# hacker-boards-refactor.net
KiCad netlist of a schematic drawn in EAGLE
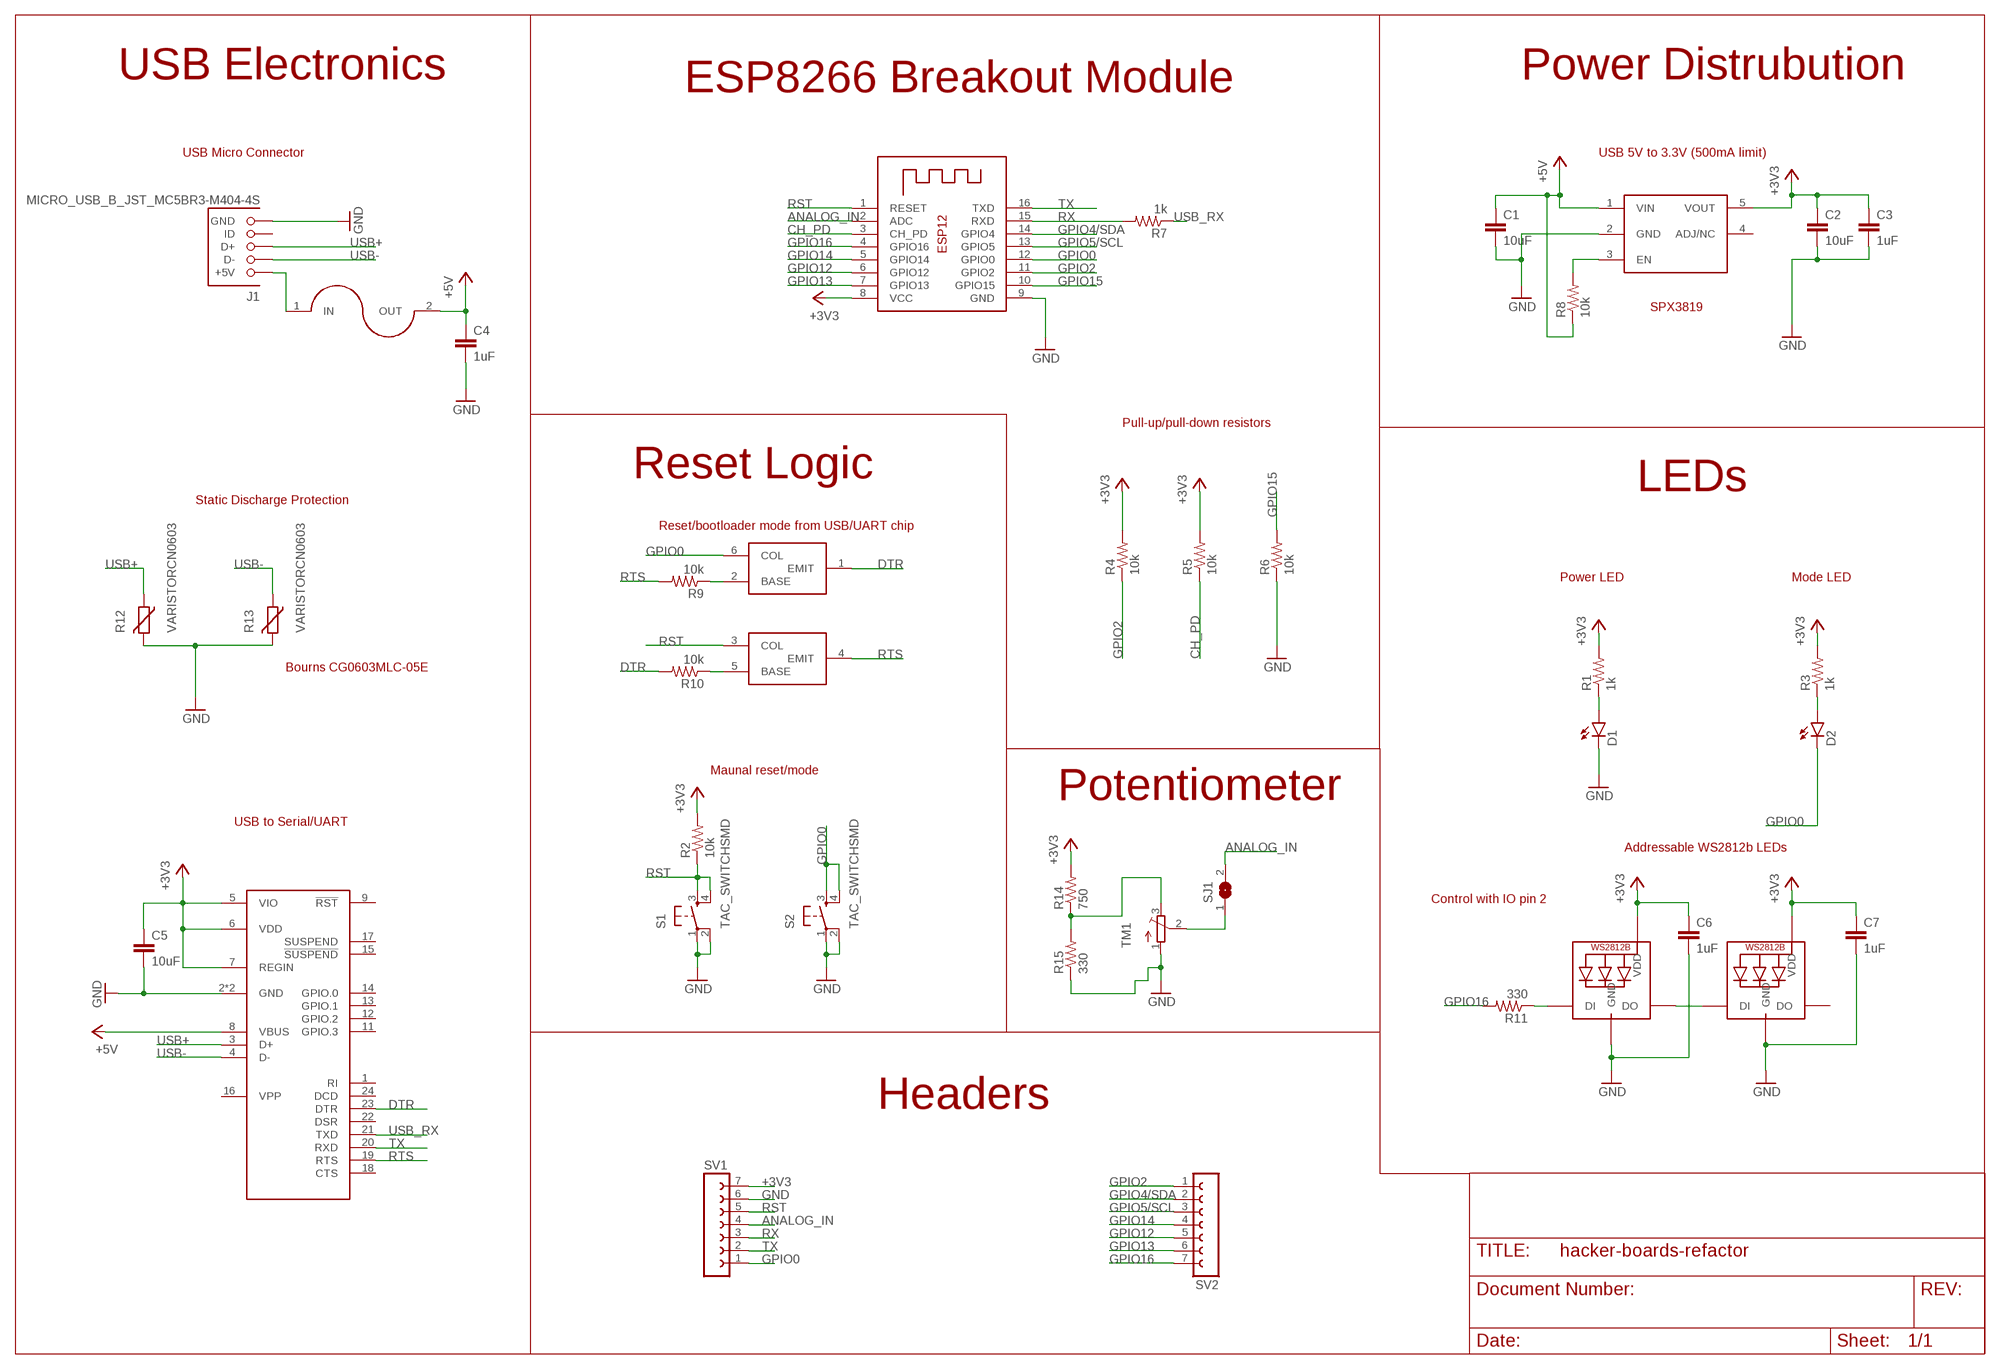
[diagram p0: schematic, sheet 1]

(export (version "E")
  (design (tool "Eeschema 10.0.6"))
  (components
    (comp (ref "C1")
      (value "10uF")
      (footprint "eagle-import:C0805")
      (libsource (lib "eagle-import") (part "C0805"))
    )
    (comp (ref "C2")
      (value "10uF")
      (footprint "eagle-import:C0805")
      (libsource (lib "eagle-import") (part "C0805"))
    )
    (comp (ref "C3")
      (value "1uF")
      (footprint "eagle-import:C0805")
      (libsource (lib "eagle-import") (part "C0805"))
    )
    (comp (ref "C4")
      (value "1uF")
      (footprint "eagle-import:C0805")
      (libsource (lib "eagle-import") (part "C0805"))
    )
    (comp (ref "C5")
      (value "10uF")
      (footprint "eagle-import:C0805")
      (libsource (lib "eagle-import") (part "C0805"))
    )
    (comp (ref "C6")
      (value "1uF")
      (footprint "eagle-import:C0805")
      (libsource (lib "eagle-import") (part "C0805"))
    )
    (comp (ref "C7")
      (value "1uF")
      (footprint "eagle-import:C0805")
      (libsource (lib "eagle-import") (part "C0805"))
    )
    (comp (ref "D1")
      (value "LED0603")
      (footprint "eagle-import:LED-0603")
      (libsource (lib "eagle-import") (part "LED0603"))
    )
    (comp (ref "D2")
      (value "LED0603")
      (footprint "eagle-import:LED-0603")
      (libsource (lib "eagle-import") (part "LED0603"))
    )
    (comp (ref "J1")
      (value "MICRO_USB_B_JST_MC5BR3-M404-4S")
      (footprint "eagle-import:USB_MICRO_B-JST-MC5BR3-M404-4S-TB")
      (libsource (lib "eagle-import") (part "MICRO_USB_B_JST_MC5BR3-M404-4S"))
    )
    (comp (ref "LED1")
      (value "WS2812B5050")
      (footprint "eagle-import:WS2812B")
      (libsource (lib "eagle-import") (part "WS2812B5050"))
    )
    (comp (ref "LED2")
      (value "WS2812B5050")
      (footprint "eagle-import:WS2812B")
      (libsource (lib "eagle-import") (part "WS2812B5050"))
    )
    (comp (ref "R1")
      (value "1k")
      (footprint "eagle-import:R0805")
      (libsource (lib "eagle-import") (part "R-US_R0805"))
    )
    (comp (ref "R2")
      (value "10k")
      (footprint "eagle-import:R0805")
      (libsource (lib "eagle-import") (part "R-US_R0805"))
    )
    (comp (ref "R3")
      (value "1k")
      (footprint "eagle-import:R0805")
      (libsource (lib "eagle-import") (part "R-US_R0805"))
    )
    (comp (ref "R4")
      (value "10k")
      (footprint "eagle-import:R0805")
      (libsource (lib "eagle-import") (part "R-US_R0805"))
    )
    (comp (ref "R5")
      (value "10k")
      (footprint "eagle-import:R0805")
      (libsource (lib "eagle-import") (part "R-US_R0805"))
    )
    (comp (ref "R6")
      (value "10k")
      (footprint "eagle-import:R0805")
      (libsource (lib "eagle-import") (part "R-US_R0805"))
    )
    (comp (ref "R7")
      (value "1k")
      (footprint "eagle-import:R0805")
      (libsource (lib "eagle-import") (part "R-US_R0805"))
    )
    (comp (ref "R8")
      (value "10k")
      (footprint "eagle-import:R0805")
      (libsource (lib "eagle-import") (part "R-US_R0805"))
    )
    (comp (ref "R9")
      (value "10k")
      (footprint "eagle-import:R0805")
      (libsource (lib "eagle-import") (part "R-US_R0805"))
    )
    (comp (ref "R10")
      (value "10k")
      (footprint "eagle-import:R0805")
      (libsource (lib "eagle-import") (part "R-US_R0805"))
    )
    (comp (ref "R11")
      (value "330")
      (footprint "eagle-import:R0805")
      (libsource (lib "eagle-import") (part "R-US_R0805"))
    )
    (comp (ref "R12")
      (value "VARISTORCN0603")
      (footprint "eagle-import:CT_CN0603")
      (libsource (lib "eagle-import") (part "VARISTORCN0603"))
    )
    (comp (ref "R13")
      (value "VARISTORCN0603")
      (footprint "eagle-import:CT_CN0603")
      (libsource (lib "eagle-import") (part "VARISTORCN0603"))
    )
    (comp (ref "R14")
      (value "750")
      (footprint "eagle-import:R0805")
      (libsource (lib "eagle-import") (part "R-US_R0805"))
    )
    (comp (ref "R15")
      (value "330")
      (footprint "eagle-import:R0805")
      (libsource (lib "eagle-import") (part "R-US_R0805"))
    )
    (comp (ref "S1")
      (value "TAC_SWITCHSMD")
      (footprint "eagle-import:TACTILE-SWITCH-SMD")
      (libsource (lib "eagle-import") (part "TAC_SWITCHSMD"))
    )
    (comp (ref "S2")
      (value "TAC_SWITCHSMD")
      (footprint "eagle-import:TACTILE-SWITCH-SMD")
      (libsource (lib "eagle-import") (part "TAC_SWITCHSMD"))
    )
    (comp (ref "SJ1") (value "SJ") (footprint "eagle-import:SJ") (libsource (lib "eagle-import") (part "SJ")))
    (comp (ref "SV1")
      (value "FE07-1")
      (footprint "eagle-import:FE07")
      (libsource (lib "eagle-import") (part "FE07-1"))
    )
    (comp (ref "SV2")
      (value "FE07-1")
      (footprint "eagle-import:FE07")
      (libsource (lib "eagle-import") (part "FE07-1"))
    )
    (comp (ref "TM1")
      (value "TRIMPOTTC33X")
      (footprint "eagle-import:TC33X")
      (libsource (lib "eagle-import") (part "TRIMPOTTC33X"))
    )
    (comp (ref "U$1")
      (value "USB-FUSE")
      (footprint "eagle-import:L1812")
      (libsource (lib "eagle-import") (part "USB-FUSE"))
    )
    (comp (ref "U$2")
      (value "AP2112")
      (footprint "eagle-import:SOT23-5L")
      (libsource (lib "eagle-import") (part "AP2112"))
    )
    (comp (ref "U$3")
      (value "CP2104")
      (footprint "eagle-import:QFN24_4X4")
      (libsource (lib "eagle-import") (part "CP2104"))
    )
    (comp (ref "U$4")
      (value "MBT3904DW1T1G")
      (footprint "eagle-import:SOT363")
      (libsource (lib "eagle-import") (part "MBT3904DW1T1G"))
    )
    (comp (ref "X1")
      (value "ESP-12")
      (footprint "eagle-import:ESP-12")
      (libsource (lib "eagle-import") (part "ESP-12"))
    )
  )
  (nets
    (net (code "1") (name "+3V3") (class "Default")
      (node (ref "C2") (pin "1") (pinfunction "1_1") (pintype "passive"))
      (node (ref "C3") (pin "1") (pinfunction "1_1") (pintype "passive"))
      (node (ref "C5") (pin "1") (pinfunction "1_1") (pintype "passive"))
      (node (ref "C6") (pin "1") (pinfunction "1_1") (pintype "passive"))
      (node (ref "C7") (pin "1") (pinfunction "1_1") (pintype "passive"))
      (node (ref "LED1") (pin "1-VDD") (pinfunction "VDD_1-VDD") (pintype "power_in"))
      (node (ref "LED2") (pin "1-VDD") (pinfunction "VDD_1-VDD") (pintype "power_in"))
      (node (ref "R1") (pin "2") (pinfunction "2_2") (pintype "passive"))
      (node (ref "R14") (pin "2") (pinfunction "2_2") (pintype "passive"))
      (node (ref "R2") (pin "2") (pinfunction "2_2") (pintype "passive"))
      (node (ref "R3") (pin "2") (pinfunction "2_2") (pintype "passive"))
      (node (ref "R4") (pin "2") (pinfunction "2_2") (pintype "passive"))
      (node (ref "R5") (pin "2") (pinfunction "2_2") (pintype "passive"))
      (node (ref "SV1") (pin "7") (pinfunction "7_7") (pintype "passive"))
      (node (ref "U$2") (pin "5") (pinfunction "VOUT_5") (pintype "bidirectional"))
      (node (ref "U$3") (pin "5") (pinfunction "VIO_5") (pintype "bidirectional"))
      (node (ref "U$3") (pin "6") (pinfunction "VDD_6") (pintype "bidirectional"))
      (node (ref "U$3") (pin "7") (pinfunction "REGIN_7") (pintype "bidirectional"))
      (node (ref "X1") (pin "8") (pinfunction "VCC_8") (pintype "power_in"))
    )
    (net (code "2") (name "+5V") (class "Default")
      (node (ref "C1") (pin "1") (pinfunction "1_1") (pintype "passive"))
      (node (ref "C4") (pin "1") (pinfunction "1_1") (pintype "passive"))
      (node (ref "R8") (pin "1") (pinfunction "1_1") (pintype "passive"))
      (node (ref "U$1") (pin "2") (pinfunction "OUT_2") (pintype "bidirectional"))
      (node (ref "U$2") (pin "1") (pinfunction "VIN_1") (pintype "bidirectional"))
      (node (ref "U$3") (pin "8") (pinfunction "VBUS_8") (pintype "bidirectional"))
    )
    (net (code "3") (name "/ANALOG_IN") (class "Default")
      (node (ref "SJ1") (pin "2") (pinfunction "2_2") (pintype "passive"))
      (node (ref "SV1") (pin "4") (pinfunction "4_4") (pintype "passive"))
      (node (ref "X1") (pin "2") (pinfunction "ADC_2") (pintype "passive"))
    )
    (net (code "4") (name "/CH_PD") (class "Default")
      (node (ref "R5") (pin "1") (pinfunction "1_1") (pintype "passive"))
      (node (ref "X1") (pin "3") (pinfunction "CH_PD_3") (pintype "input"))
    )
    (net (code "5") (name "/DTR") (class "Default")
      (node (ref "R10") (pin "2") (pinfunction "2_2") (pintype "passive"))
      (node (ref "U$3") (pin "23") (pinfunction "DTR_23") (pintype "bidirectional"))
      (node (ref "U$4") (pin "1") (pinfunction "EMIT_1") (pintype "bidirectional"))
    )
    (net (code "6") (name "/GPIO0") (class "Default")
      (node (ref "D2") (pin "C") (pinfunction "C_C") (pintype "passive"))
      (node (ref "S2") (pin "3") (pinfunction "3_3") (pintype "passive"))
      (node (ref "S2") (pin "4") (pinfunction "4_4") (pintype "passive"))
      (node (ref "SV1") (pin "1") (pinfunction "1_1") (pintype "passive"))
      (node (ref "U$4") (pin "6") (pinfunction "COL_6") (pintype "bidirectional"))
      (node (ref "X1") (pin "12") (pinfunction "GPIO0_12") (pintype "bidirectional"))
    )
    (net (code "7") (name "/GPIO2") (class "Default")
      (node (ref "R4") (pin "1") (pinfunction "1_1") (pintype "passive"))
      (node (ref "SV2") (pin "1") (pinfunction "1_1") (pintype "passive"))
      (node (ref "X1") (pin "11") (pinfunction "GPIO2_11") (pintype "bidirectional"))
    )
    (net (code "8") (name "/GPIO4{slash}SDA") (class "Default")
      (node (ref "SV2") (pin "2") (pinfunction "2_2") (pintype "passive"))
      (node (ref "X1") (pin "14") (pinfunction "GPIO4_14") (pintype "bidirectional"))
    )
    (net (code "9") (name "/GPIO5{slash}SCL") (class "Default")
      (node (ref "SV2") (pin "3") (pinfunction "3_3") (pintype "passive"))
      (node (ref "X1") (pin "13") (pinfunction "GPIO5_13") (pintype "bidirectional"))
    )
    (net (code "10") (name "/GPIO12") (class "Default")
      (node (ref "SV2") (pin "5") (pinfunction "5_5") (pintype "passive"))
      (node (ref "X1") (pin "6") (pinfunction "GPIO12_6") (pintype "bidirectional"))
    )
    (net (code "11") (name "/GPIO13") (class "Default")
      (node (ref "SV2") (pin "6") (pinfunction "6_6") (pintype "passive"))
      (node (ref "X1") (pin "7") (pinfunction "GPIO13_7") (pintype "bidirectional"))
    )
    (net (code "12") (name "/GPIO14") (class "Default")
      (node (ref "SV2") (pin "4") (pinfunction "4_4") (pintype "passive"))
      (node (ref "X1") (pin "5") (pinfunction "GPIO14_5") (pintype "bidirectional"))
    )
    (net (code "13") (name "/GPIO15") (class "Default")
      (node (ref "R6") (pin "2") (pinfunction "2_2") (pintype "passive"))
      (node (ref "X1") (pin "10") (pinfunction "GPIO15_10") (pintype "bidirectional"))
    )
    (net (code "14") (name "/GPIO16") (class "Default")
      (node (ref "R11") (pin "2") (pinfunction "2_2") (pintype "passive"))
      (node (ref "SV2") (pin "7") (pinfunction "7_7") (pintype "passive"))
      (node (ref "X1") (pin "4") (pinfunction "GPIO16_4") (pintype "bidirectional"))
    )
    (net (code "15") (name "/RST") (class "Default")
      (node (ref "R2") (pin "1") (pinfunction "1_1") (pintype "passive"))
      (node (ref "S1") (pin "3") (pinfunction "3_3") (pintype "passive"))
      (node (ref "S1") (pin "4") (pinfunction "4_4") (pintype "passive"))
      (node (ref "SV1") (pin "5") (pinfunction "5_5") (pintype "passive"))
      (node (ref "U$4") (pin "3") (pinfunction "COL_3") (pintype "bidirectional"))
      (node (ref "X1") (pin "1") (pinfunction "RESET_1") (pintype "input"))
    )
    (net (code "16") (name "/RTS") (class "Default")
      (node (ref "R9") (pin "2") (pinfunction "2_2") (pintype "passive"))
      (node (ref "U$3") (pin "19") (pinfunction "RTS_19") (pintype "bidirectional"))
      (node (ref "U$4") (pin "4") (pinfunction "EMIT_4") (pintype "bidirectional"))
    )
    (net (code "17") (name "/RX") (class "Default")
      (node (ref "R7") (pin "2") (pinfunction "2_2") (pintype "passive"))
      (node (ref "SV1") (pin "3") (pinfunction "3_3") (pintype "passive"))
      (node (ref "X1") (pin "15") (pinfunction "RXD_15") (pintype "input"))
    )
    (net (code "18") (name "/TX") (class "Default")
      (node (ref "SV1") (pin "2") (pinfunction "2_2") (pintype "passive"))
      (node (ref "U$3") (pin "20") (pinfunction "RXD_20") (pintype "bidirectional"))
      (node (ref "X1") (pin "16") (pinfunction "TXD_16") (pintype "output"))
    )
    (net (code "19") (name "/USB+") (class "Default")
      (node (ref "J1") (pin "3") (pinfunction "D+_3") (pintype "bidirectional"))
      (node (ref "R12") (pin "1") (pinfunction "1_1") (pintype "passive"))
      (node (ref "U$3") (pin "3") (pinfunction "D+_3") (pintype "bidirectional"))
    )
    (net (code "20") (name "/USB-") (class "Default")
      (node (ref "J1") (pin "2") (pinfunction "D-_2") (pintype "bidirectional"))
      (node (ref "R13") (pin "1") (pinfunction "1_1") (pintype "passive"))
      (node (ref "U$3") (pin "4") (pinfunction "D-_4") (pintype "bidirectional"))
    )
    (net (code "21") (name "/USB_RX") (class "Default")
      (node (ref "R7") (pin "1") (pinfunction "1_1") (pintype "passive"))
      (node (ref "U$3") (pin "21") (pinfunction "TXD_21") (pintype "bidirectional"))
    )
    (net (code "22") (name "GND") (class "Default")
      (node (ref "C1") (pin "2") (pinfunction "2_2") (pintype "passive"))
      (node (ref "C2") (pin "2") (pinfunction "2_2") (pintype "passive"))
      (node (ref "C3") (pin "2") (pinfunction "2_2") (pintype "passive"))
      (node (ref "C4") (pin "2") (pinfunction "2_2") (pintype "passive"))
      (node (ref "C5") (pin "2") (pinfunction "2_2") (pintype "passive"))
      (node (ref "C6") (pin "2") (pinfunction "2_2") (pintype "passive"))
      (node (ref "C7") (pin "2") (pinfunction "2_2") (pintype "passive"))
      (node (ref "D1") (pin "C") (pinfunction "C_C") (pintype "passive"))
      (node (ref "J1") (pin "5") (pinfunction "GND_5") (pintype "bidirectional"))
      (node (ref "LED1") (pin "3-GND") (pinfunction "GND_3-GND") (pintype "power_in"))
      (node (ref "LED2") (pin "3-GND") (pinfunction "GND_3-GND") (pintype "power_in"))
      (node (ref "R12") (pin "2") (pinfunction "2_2") (pintype "passive"))
      (node (ref "R13") (pin "2") (pinfunction "2_2") (pintype "passive"))
      (node (ref "R15") (pin "1") (pinfunction "1_1") (pintype "passive"))
      (node (ref "R6") (pin "1") (pinfunction "1_1") (pintype "passive"))
      (node (ref "S1") (pin "1") (pinfunction "1_1") (pintype "passive"))
      (node (ref "S1") (pin "2") (pinfunction "2_2") (pintype "passive"))
      (node (ref "S2") (pin "1") (pinfunction "1_1") (pintype "passive"))
      (node (ref "S2") (pin "2") (pinfunction "2_2") (pintype "passive"))
      (node (ref "SV1") (pin "6") (pinfunction "6_6") (pintype "passive"))
      (node (ref "TM1") (pin "1") (pinfunction "A_1") (pintype "passive"))
      (node (ref "U$2") (pin "2") (pinfunction "GND_2") (pintype "bidirectional"))
      (node (ref "U$3") (pin "2") (pinfunction "GND_2") (pintype "bidirectional"))
      (node (ref "U$3") (pin "25") (pinfunction "GND_25") (pintype "bidirectional"))
      (node (ref "X1") (pin "9") (pinfunction "GND_9") (pintype "power_in"))
    )
    (net (code "23") (name "Net-(D1-PadA)") (class "Default")
      (node (ref "D1") (pin "A") (pinfunction "A_A") (pintype "passive"))
      (node (ref "R1") (pin "1") (pinfunction "1_1") (pintype "passive"))
    )
    (net (code "24") (name "Net-(D2-PadA)") (class "Default")
      (node (ref "D2") (pin "A") (pinfunction "A_A") (pintype "passive"))
      (node (ref "R3") (pin "1") (pinfunction "1_1") (pintype "passive"))
    )
    (net (code "25") (name "Net-(J1-+5V)") (class "Default")
      (node (ref "J1") (pin "1") (pinfunction "+5V_1") (pintype "bidirectional"))
      (node (ref "U$1") (pin "1") (pinfunction "IN_1") (pintype "bidirectional"))
    )
    (net (code "26") (name "Net-(LED1-DI)") (class "Default")
      (node (ref "LED1") (pin "4-DIN") (pinfunction "DI_4-DIN") (pintype "input"))
      (node (ref "R11") (pin "1") (pinfunction "1_1") (pintype "passive"))
    )
    (net (code "27") (name "Net-(LED1-DO)") (class "Default")
      (node (ref "LED1") (pin "2-DOUT") (pinfunction "DO_2-DOUT") (pintype "output"))
      (node (ref "LED2") (pin "4-DIN") (pinfunction "DI_4-DIN") (pintype "input"))
    )
    (net (code "28") (name "Net-(TM1-E)") (class "Default")
      (node (ref "R14") (pin "1") (pinfunction "1_1") (pintype "passive"))
      (node (ref "R15") (pin "2") (pinfunction "2_2") (pintype "passive"))
      (node (ref "TM1") (pin "3") (pinfunction "E_3") (pintype "passive"))
    )
    (net (code "29") (name "Net-(TM1-S)") (class "Default")
      (node (ref "SJ1") (pin "1") (pinfunction "1_1") (pintype "passive"))
      (node (ref "TM1") (pin "2") (pinfunction "S_2") (pintype "passive"))
    )
    (net (code "30") (name "Net-(U$2-EN)") (class "Default")
      (node (ref "R8") (pin "2") (pinfunction "2_2") (pintype "passive"))
      (node (ref "U$2") (pin "3") (pinfunction "EN_3") (pintype "bidirectional"))
    )
    (net (code "31") (name "Net-(U$4A-BASE)") (class "Default")
      (node (ref "R9") (pin "1") (pinfunction "1_1") (pintype "passive"))
      (node (ref "U$4") (pin "2") (pinfunction "BASE_2") (pintype "bidirectional"))
    )
    (net (code "32") (name "Net-(U$4B-BASE)") (class "Default")
      (node (ref "R10") (pin "1") (pinfunction "1_1") (pintype "passive"))
      (node (ref "U$4") (pin "5") (pinfunction "BASE_5") (pintype "bidirectional"))
    )
    (net (code "33") (name "unconnected-(J1-ID-Pad4)") (class "Default")
      (node (ref "J1") (pin "4") (pinfunction "ID_4") (pintype "bidirectional"))
    )
    (net (code "34") (name "unconnected-(LED2-DO-Pad2-DOUT)") (class "Default")
      (node (ref "LED2") (pin "2-DOUT") (pinfunction "DO_2-DOUT") (pintype "output"))
    )
    (net (code "35") (name "unconnected-(U$2-ADJ{slash}NC-Pad4)") (class "Default")
      (node (ref "U$2") (pin "4") (pinfunction "ADJ/NC_4") (pintype "bidirectional"))
    )
    (net (code "36") (name "unconnected-(U$3-CTS-Pad18)") (class "Default")
      (node (ref "U$3") (pin "18") (pinfunction "CTS_18") (pintype "bidirectional"))
    )
    (net (code "37") (name "unconnected-(U$3-DCD-Pad24)") (class "Default")
      (node (ref "U$3") (pin "24") (pinfunction "DCD_24") (pintype "bidirectional"))
    )
    (net (code "38") (name "unconnected-(U$3-DSR-Pad22)") (class "Default")
      (node (ref "U$3") (pin "22") (pinfunction "DSR_22") (pintype "bidirectional"))
    )
    (net (code "39") (name "unconnected-(U$3-GPIO.0-Pad14)") (class "Default")
      (node (ref "U$3") (pin "14") (pinfunction "GPIO.0_14") (pintype "bidirectional"))
    )
    (net (code "40") (name "unconnected-(U$3-GPIO.1-Pad13)") (class "Default")
      (node (ref "U$3") (pin "13") (pinfunction "GPIO.1_13") (pintype "bidirectional"))
    )
    (net (code "41") (name "unconnected-(U$3-GPIO.2-Pad12)") (class "Default")
      (node (ref "U$3") (pin "12") (pinfunction "GPIO.2_12") (pintype "bidirectional"))
    )
    (net (code "42") (name "unconnected-(U$3-GPIO.3-Pad11)") (class "Default")
      (node (ref "U$3") (pin "11") (pinfunction "GPIO.3_11") (pintype "bidirectional"))
    )
    (net (code "43") (name "unconnected-(U$3-RI-Pad1)") (class "Default")
      (node (ref "U$3") (pin "1") (pinfunction "RI_1") (pintype "bidirectional"))
    )
    (net (code "44") (name "unconnected-(U$3-SUSPEND-Pad17)") (class "Default")
      (node (ref "U$3") (pin "17") (pinfunction "SUSPEND_17") (pintype "bidirectional"))
    )
    (net (code "45") (name "unconnected-(U$3-VPP-Pad16)") (class "Default")
      (node (ref "U$3") (pin "16") (pinfunction "VPP_16") (pintype "input"))
    )
    (net (code "46") (name "unconnected-(U$3-~{RST}-Pad9)") (class "Default")
      (node (ref "U$3") (pin "9") (pinfunction "~{RST}_9") (pintype "bidirectional"))
    )
    (net (code "47") (name "unconnected-(U$3-~{SUSPEND}-Pad15)") (class "Default")
      (node (ref "U$3") (pin "15") (pinfunction "~{SUSPEND}_15") (pintype "bidirectional"))
    )
  )
)
